# ocxo.net
KiCad netlist of a schematic drawn in Altium Designer
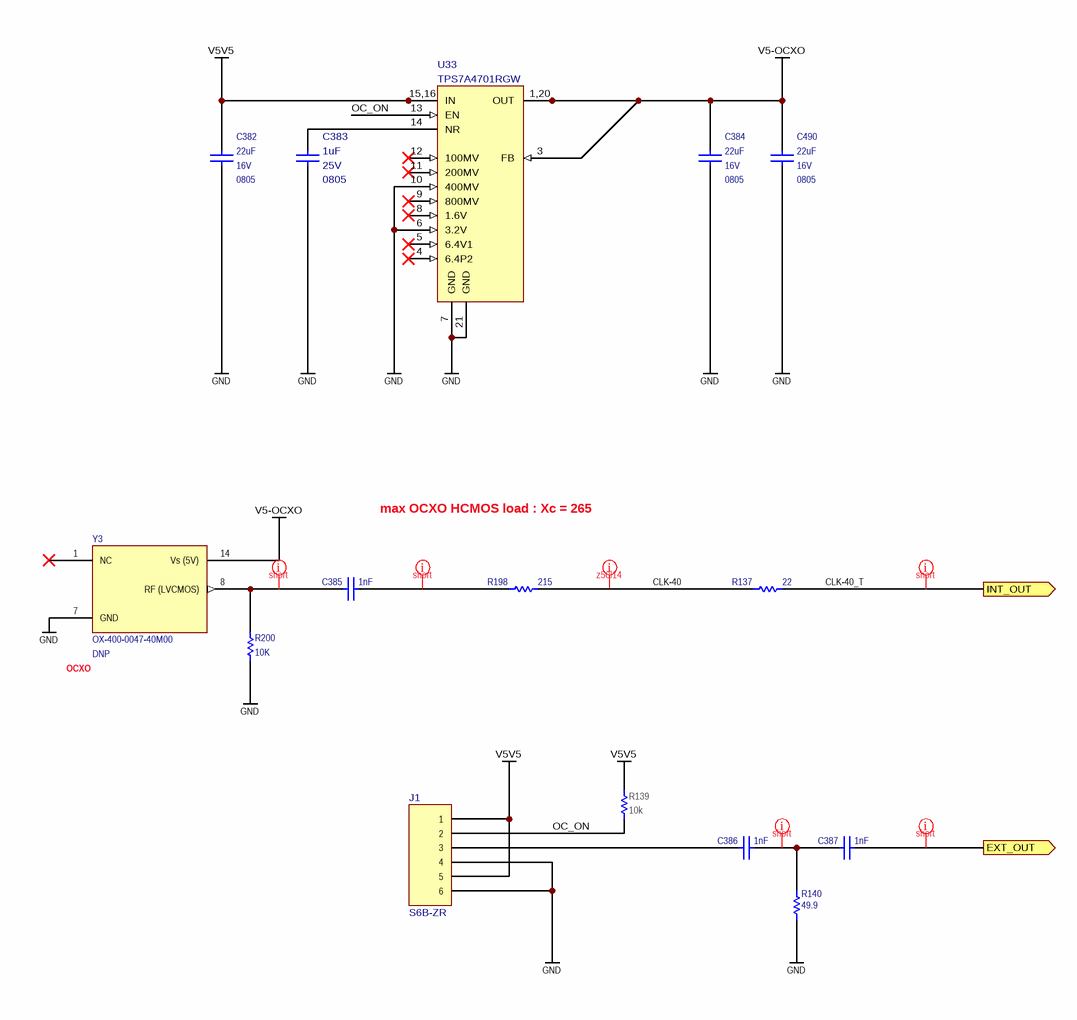
[diagram p0: ocxo.SchDoc]

(export (version "E")
  (design (tool "Eeschema 10.0.6"))
  (components
    (comp (ref "C382")
      (value "22uF")
      (footprint "generic:CAPC200X125X145L45N")
      (description "Ceramic Capacitor 22uF ±10% 16V X5R 0805")
      (fields
        (field (name "MANUFACTURER") "Samsung")
        (field (name "VOLTAGE") "16V")
        (field (name "PACKAGE") "0805")
        (field (name "TOLERANCE") "±10%")
      )
      (libsource (lib "generic") (part "CAP 0603"))
    )
    (comp (ref "C383")
      (value "1uF")
      (footprint "CAPC200X125X145L45N")
      (description "Ceramic Capacitor 1uF ±10% 25V X7R 0805")
      (fields
        (field (name "MANUFACTURER") "Taiyo Yuden")
        (field (name "TOLERANCE") "±10%")
        (field (name "PACKAGE") "0805")
        (field (name "VOLTAGE") "25V")
      )
      (libsource (lib "capacitors") (part "CAP"))
    )
    (comp (ref "C384")
      (value "22uF")
      (footprint "generic:CAPC200X125X145L45N")
      (description "Ceramic Capacitor 22uF ±10% 16V X5R 0805")
      (fields
        (field (name "MANUFACTURER") "Samsung")
        (field (name "VOLTAGE") "16V")
        (field (name "PACKAGE") "0805")
        (field (name "TOLERANCE") "±10%")
      )
      (libsource (lib "generic") (part "CAP 0603"))
    )
    (comp (ref "C385")
      (value "1nF")
      (footprint "CAPC100X50X55L25N")
      (description "Ceramic Capacitor 1nF ±5% 50V NP0 0402")
      (fields (field (name "VOLTAGE") "50V") (field (name "MANUFACTURER") "TDK"))
      (libsource (lib "Graviton") (part "CAP 0402"))
    )
    (comp (ref "C386")
      (value "1nF")
      (footprint "CAPC100X50X55L25N")
      (description "Ceramic Capacitor 1nF ±5% 50V NP0 0402")
      (fields (field (name "VOLTAGE") "50V") (field (name "MANUFACTURER") "TDK"))
      (libsource (lib "Graviton") (part "CAP 0402"))
    )
    (comp (ref "C387")
      (value "1nF")
      (footprint "CAPC100X50X55L25N")
      (description "Ceramic Capacitor 1nF ±5% 50V NP0 0402")
      (fields (field (name "VOLTAGE") "50V") (field (name "MANUFACTURER") "TDK"))
      (libsource (lib "Graviton") (part "CAP 0402"))
    )
    (comp (ref "C490")
      (value "22uF")
      (footprint "generic:CAPC200X125X145L45N")
      (description "Ceramic Capacitor 22uF ±10% 16V X5R 0805")
      (fields
        (field (name "MANUFACTURER") "Samsung")
        (field (name "VOLTAGE") "16V")
        (field (name "PACKAGE") "0805")
        (field (name "TOLERANCE") "±10%")
      )
      (libsource (lib "generic") (part "CAP 0603"))
    )
    (comp (ref "J1")
      (value "S6B-ZR")
      (footprint "jst:S6B-ZR")
      (description "1.5mm pitch right angle 6-position")
      (fields (field (name "MANUFACTURER") "JST"))
      (libsource (lib "jst") (part "S6B-ZR"))
    )
    (comp (ref "R137")
      (value "22")
      (footprint "RESC1005X40N")
      (description "Thick Film Resistor 22 ±1% 0402")
      (fields (field (name "MANUFACTURER") "Yageo") (field (name "TOLERANCE") "±1%"))
      (libsource (lib "Graviton") (part "RES 0402"))
    )
    (comp (ref "R139")
      (value "10k")
      (footprint "RESC1005X40N")
      (description "Thick Film Resistor 10k ±1% 0.1W 50V 0402")
      (fields (field (name "MANUFACTURER") "Panasonic") (field (name "TOLERANCE") "±1%"))
      (libsource (lib "generic") (part "RES"))
    )
    (comp (ref "R140")
      (value "49.9")
      (footprint "RESC1005X40N")
      (description "Thin Film Resistor 49.9 ±0.1% 0402")
      (fields (field (name "MANUFACTURER") "Panasonic") (field (name "TOLERANCE") "±0.1%"))
      (libsource (lib "Graviton") (part "RES 0402"))
    )
    (comp (ref "R198")
      (value "215")
      (footprint "RESC1005X40N")
      (description "Thick Film Resistor 215 ±1% 0402")
      (fields (field (name "MANUFACTURER") "Yageo") (field (name "TOLERANCE") "±1%"))
      (libsource (lib "Graviton") (part "RES 0402"))
    )
    (comp (ref "R200")
      (value "10K")
      (footprint "RESC1005X40N")
      (description "Thick Film Resistor 10k ±1% 0.1W 50V 0402")
      (fields (field (name "MANUFACTURER") "Panasonic") (field (name "TOLERANCE") "±1%"))
      (libsource (lib "Graviton") (part "RES 0402"))
    )
    (comp (ref "U33")
      (value "TPS7A4701RGW")
      (footprint "QFN65P500X500X100-21N")
      (description "Low-Dropout Linear Regulator 20-VQFN")
      (fields (field (name "MANUFACTURER") "Texas Instruments"))
      (libsource (lib "ti") (part "TPS7A4701RGW_1"))
    )
    (comp (ref "Y3")
      (value "OX-400-0047-40M00")
      (footprint "G125")
      (description "Oven Controlled Precision Oscillator, 10MHz")
      (fields (field (name "MANUFACTURER") "Vectron") (field (name "DO NOT PLACE") "DNP"))
      (libsource (lib "vectron") (part "OX-400-0047-40M00"))
    )
  )
  (nets
    (net (code "1") (name "/CLK-40") (class "Default")
      (node (ref "R137") (pin "1") (pinfunction "1_1") (pintype "passive"))
      (node (ref "R198") (pin "2") (pinfunction "2_2") (pintype "passive"))
    )
    (net (code "2") (name "/CLK-40_T") (class "Default")
      (node (ref "R137") (pin "2") (pinfunction "2_2") (pintype "passive"))
    )
    (net (code "3") (name "/EXT_OUT") (class "Default")
      (node (ref "C387") (pin "1") (pinfunction "1_1") (pintype "passive"))
    )
    (net (code "4") (name "/OC_ON") (class "Default")
      (node (ref "J1") (pin "2") (pinfunction "2_2") (pintype "passive"))
      (node (ref "R139") (pin "1") (pinfunction "1_1") (pintype "passive"))
      (node (ref "U33") (pin "13") (pinfunction "EN_13") (pintype "input"))
    )
    (net (code "5") (name "GND") (class "Default")
      (node (ref "C382") (pin "1") (pinfunction "1_1") (pintype "passive"))
      (node (ref "C383") (pin "2") (pinfunction "2_2") (pintype "passive"))
      (node (ref "C384") (pin "1") (pinfunction "1_1") (pintype "passive"))
      (node (ref "C490") (pin "1") (pinfunction "1_1") (pintype "passive"))
      (node (ref "J1") (pin "4") (pinfunction "4_4") (pintype "passive"))
      (node (ref "J1") (pin "6") (pinfunction "6_6") (pintype "passive"))
      (node (ref "R140") (pin "2") (pinfunction "2_2") (pintype "passive"))
      (node (ref "R200") (pin "1") (pinfunction "1_1") (pintype "passive"))
      (node (ref "U33") (pin "10") (pinfunction "400MV_10") (pintype "input"))
      (node (ref "U33") (pin "21") (pinfunction "GND_21") (pintype "power_in"))
      (node (ref "U33") (pin "6") (pinfunction "3.2V_6") (pintype "input"))
      (node (ref "U33") (pin "7") (pinfunction "GND_7") (pintype "power_in"))
      (node (ref "Y3") (pin "7") (pinfunction "GND_7") (pintype "power_in"))
    )
    (net (code "6") (name "Net-(C385-Pad1)") (class "Default")
      (node (ref "C385") (pin "1") (pinfunction "1_1") (pintype "passive"))
      (node (ref "R198") (pin "1") (pinfunction "1_1") (pintype "passive"))
    )
    (net (code "7") (name "Net-(C386-Pad1)") (class "Default")
      (node (ref "C386") (pin "1") (pinfunction "1_1") (pintype "passive"))
      (node (ref "C387") (pin "2") (pinfunction "2_2") (pintype "passive"))
      (node (ref "R140") (pin "1") (pinfunction "1_1") (pintype "passive"))
    )
    (net (code "8") (name "Net-(C386-Pad2)") (class "Default")
      (node (ref "C386") (pin "2") (pinfunction "2_2") (pintype "passive"))
      (node (ref "J1") (pin "3") (pinfunction "3_3") (pintype "passive"))
    )
    (net (code "9") (name "Net-(U33-NR)") (class "Default")
      (node (ref "C383") (pin "1") (pinfunction "1_1") (pintype "passive"))
      (node (ref "U33") (pin "14") (pinfunction "NR_14") (pintype "passive"))
    )
    (net (code "10") (name "Net-(Y3-RF_(LVCMOS))") (class "Default")
      (node (ref "C385") (pin "2") (pinfunction "2_2") (pintype "passive"))
      (node (ref "R200") (pin "2") (pinfunction "2_2") (pintype "passive"))
      (node (ref "Y3") (pin "8") (pinfunction "RF_(LVCMOS)_8") (pintype "output"))
    )
    (net (code "11") (name "V5-OCXO") (class "Default")
      (node (ref "C384") (pin "2") (pinfunction "2_2") (pintype "passive"))
      (node (ref "C490") (pin "2") (pinfunction "2_2") (pintype "passive"))
      (node (ref "U33") (pin "1") (pinfunction "OUT_1") (pintype "passive"))
      (node (ref "U33") (pin "20") (pinfunction "OUT_20") (pintype "passive"))
      (node (ref "U33") (pin "3") (pinfunction "FB_3") (pintype "input"))
      (node (ref "Y3") (pin "14") (pinfunction "Vs_(5V)_14") (pintype "power_in"))
    )
    (net (code "12") (name "V5V5") (class "Default")
      (node (ref "C382") (pin "2") (pinfunction "2_2") (pintype "passive"))
      (node (ref "J1") (pin "1") (pinfunction "1_1") (pintype "passive"))
      (node (ref "J1") (pin "5") (pinfunction "5_5") (pintype "passive"))
      (node (ref "R139") (pin "2") (pinfunction "2_2") (pintype "passive"))
      (node (ref "U33") (pin "15") (pinfunction "IN_15") (pintype "passive"))
      (node (ref "U33") (pin "16") (pinfunction "IN_16") (pintype "passive"))
    )
    (net (code "13") (name "unconnected-(U33-1.6V-Pad8)") (class "Default")
      (node (ref "U33") (pin "8") (pinfunction "1.6V_8") (pintype "input+no_connect"))
    )
    (net (code "14") (name "unconnected-(U33-6.4P2-Pad4)") (class "Default")
      (node (ref "U33") (pin "4") (pinfunction "6.4P2_4") (pintype "input+no_connect"))
    )
    (net (code "15") (name "unconnected-(U33-6.4V1-Pad5)") (class "Default")
      (node (ref "U33") (pin "5") (pinfunction "6.4V1_5") (pintype "input+no_connect"))
    )
    (net (code "16") (name "unconnected-(U33-100MV-Pad12)") (class "Default")
      (node (ref "U33") (pin "12") (pinfunction "100MV_12") (pintype "input+no_connect"))
    )
    (net (code "17") (name "unconnected-(U33-200MV-Pad11)") (class "Default")
      (node (ref "U33") (pin "11") (pinfunction "200MV_11") (pintype "input+no_connect"))
    )
    (net (code "18") (name "unconnected-(U33-800MV-Pad9)") (class "Default")
      (node (ref "U33") (pin "9") (pinfunction "800MV_9") (pintype "input+no_connect"))
    )
    (net (code "19") (name "unconnected-(Y3-NC-Pad1)") (class "Default")
      (node (ref "Y3") (pin "1") (pinfunction "NC_1") (pintype "passive+no_connect"))
    )
  )
)
